# Sheet2.net
KiCad netlist of a schematic drawn in Altium Designer
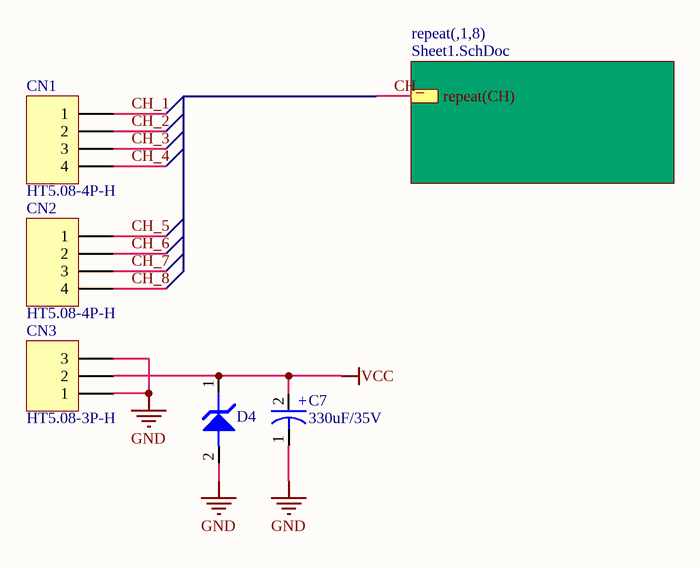
[diagram p0: Sheet2.SchDoc]

(export (version "E")
  (design (tool "Eeschema 10.0.6"))
  (components
    (comp (ref "C7")
      (value "330uF/35V")
      (footprint "CA10X16P5")
      (description "CAP 35V 20% 330uF 10X16X0.6MM ROHS，7000hours")
      (fields
        (field (name "MANUFACTURER") "NIPPON CHEMI-CON")
        (field (name "Comment") "CAPACITOR 330uF 20% 35V 10mmX16mm")
      )
      (libsource (lib "Enlogic") (part "CAPACITOR"))
    )
    (comp (ref "CN1")
      (value "HT5.08-4P-H")
      (footprint "HT5.08-4P-H")
      (description "Header, 4-Pin")
      (libsource (lib "Enlogic_CN") (part "Header 4"))
    )
    (comp (ref "CN2")
      (value "HT5.08-4P-H")
      (footprint "HT5.08-4P-H")
      (description "Header, 4-Pin")
      (libsource (lib "Enlogic_CN") (part "Header 4"))
    )
    (comp (ref "CN3")
      (value "HT5.08-3P-H")
      (footprint "HT5.08-3P-H")
      (description "Header, 3-Pin")
      (fields (field (name "PUBLISHER") "Altium Limited"))
      (libsource (lib "Miscellaneous Connectors") (part "Header 3"))
    )
    (comp (ref "D4")
      (value "SMAJ5.0A")
      (footprint "SMA")
      (fields (field (name "MANUFACTURER") "Bourns"))
      (libsource (lib "Enlogic") (part "ZENER"))
    )
  )
  (nets
    (net (code "2") (name "/CH_1") (class "Default")
      (node (ref "CN1") (pin "1") (pinfunction "1_1") (pintype "passive"))
    )
    (net (code "3") (name "/CH_2") (class "Default")
      (node (ref "CN1") (pin "2") (pinfunction "2_2") (pintype "passive"))
    )
    (net (code "4") (name "/CH_3") (class "Default")
      (node (ref "CN1") (pin "3") (pinfunction "3_3") (pintype "passive"))
    )
    (net (code "5") (name "/CH_4") (class "Default")
      (node (ref "CN1") (pin "4") (pinfunction "4_4") (pintype "passive"))
    )
    (net (code "6") (name "/CH_5") (class "Default")
      (node (ref "CN2") (pin "1") (pinfunction "1_1") (pintype "passive"))
    )
    (net (code "7") (name "/CH_6") (class "Default")
      (node (ref "CN2") (pin "2") (pinfunction "2_2") (pintype "passive"))
    )
    (net (code "8") (name "/CH_7") (class "Default")
      (node (ref "CN2") (pin "3") (pinfunction "3_3") (pintype "passive"))
    )
    (net (code "9") (name "/CH_8") (class "Default")
      (node (ref "CN2") (pin "4") (pinfunction "4_4") (pintype "passive"))
    )
    (net (code "10") (name "GND") (class "Default")
      (node (ref "C7") (pin "1") (pinfunction "1_1") (pintype "passive"))
      (node (ref "CN3") (pin "1") (pinfunction "1_1") (pintype "passive"))
      (node (ref "CN3") (pin "3") (pinfunction "3_3") (pintype "passive"))
      (node (ref "D4") (pin "2") (pintype "passive"))
    )
    (net (code "11") (name "VCC") (class "Default")
      (node (ref "C7") (pin "2") (pinfunction "2_2") (pintype "passive"))
      (node (ref "CN3") (pin "2") (pinfunction "2_2") (pintype "passive"))
      (node (ref "D4") (pin "1") (pintype "passive"))
    )
  )
)
